# v4_3.net
KiCad netlist of a schematic drawn in EAGLE
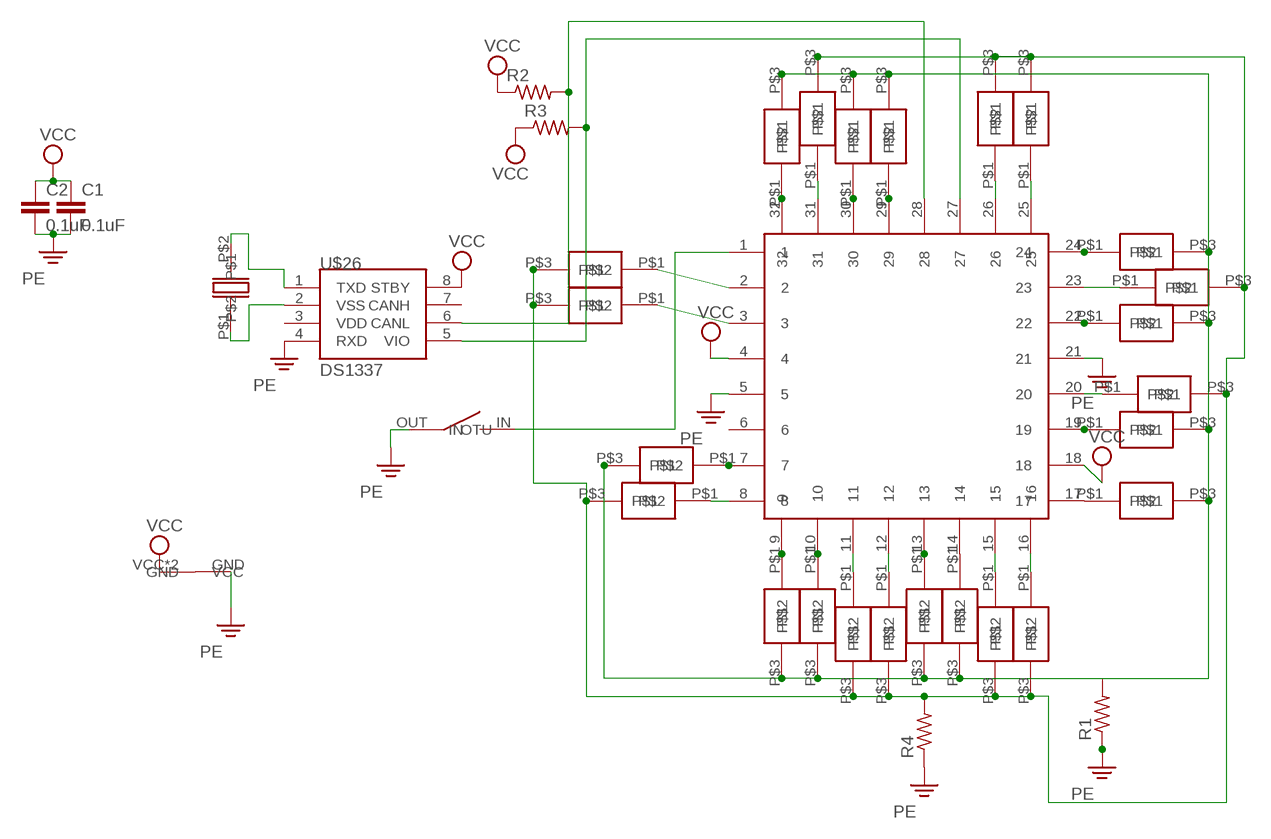
[diagram p0: schematic, sheet 1]

(export (version "E")
  (design (tool "Eeschema 10.0.6"))
  (components
    (comp (ref "C1")
      (value "0.1uF")
      (footprint "eagle-import:C0805K")
      (libsource (lib "eagle-import") (part "C-EUC0805K"))
    )
    (comp (ref "C2")
      (value "0.1uF")
      (footprint "eagle-import:C0805K")
      (libsource (lib "eagle-import") (part "C-EUC0805K"))
    )
    (comp (ref "R1")
      (value "R-US_R0805")
      (footprint "eagle-import:R0805")
      (libsource (lib "eagle-import") (part "R-US_R0805"))
    )
    (comp (ref "R2")
      (value "R-US_R0805")
      (footprint "eagle-import:R0805")
      (libsource (lib "eagle-import") (part "R-US_R0805"))
    )
    (comp (ref "R3")
      (value "R-US_R0805")
      (footprint "eagle-import:R0805")
      (libsource (lib "eagle-import") (part "R-US_R0805"))
    )
    (comp (ref "R4")
      (value "R-US_R0805")
      (footprint "eagle-import:R0805")
      (libsource (lib "eagle-import") (part "R-US_R0805"))
    )
    (comp (ref "U$1")
      (value "SMDLED")
      (footprint "eagle-import:SMDLED")
      (libsource (lib "eagle-import") (part "SMDLED"))
    )
    (comp (ref "U$2")
      (value "SMDLED")
      (footprint "eagle-import:SMDLED")
      (libsource (lib "eagle-import") (part "SMDLED"))
    )
    (comp (ref "U$3")
      (value "SMDLED")
      (footprint "eagle-import:SMDLED")
      (libsource (lib "eagle-import") (part "SMDLED"))
    )
    (comp (ref "U$4")
      (value "SMDLED")
      (footprint "eagle-import:SMDLED")
      (libsource (lib "eagle-import") (part "SMDLED"))
    )
    (comp (ref "U$5")
      (value "SMDLED")
      (footprint "eagle-import:SMDLED")
      (libsource (lib "eagle-import") (part "SMDLED"))
    )
    (comp (ref "U$6")
      (value "SMDLED")
      (footprint "eagle-import:SMDLED")
      (libsource (lib "eagle-import") (part "SMDLED"))
    )
    (comp (ref "U$7")
      (value "SMDLED")
      (footprint "eagle-import:SMDLED")
      (libsource (lib "eagle-import") (part "SMDLED"))
    )
    (comp (ref "U$8")
      (value "SMDLED")
      (footprint "eagle-import:SMDLED")
      (libsource (lib "eagle-import") (part "SMDLED"))
    )
    (comp (ref "U$9")
      (value "SMDLED")
      (footprint "eagle-import:SMDLED")
      (libsource (lib "eagle-import") (part "SMDLED"))
    )
    (comp (ref "U$10")
      (value "SMDLED")
      (footprint "eagle-import:SMDLED")
      (libsource (lib "eagle-import") (part "SMDLED"))
    )
    (comp (ref "U$11")
      (value "SMDLED")
      (footprint "eagle-import:SMDLED")
      (libsource (lib "eagle-import") (part "SMDLED"))
    )
    (comp (ref "U$12")
      (value "SMDLED")
      (footprint "eagle-import:SMDLED")
      (libsource (lib "eagle-import") (part "SMDLED"))
    )
    (comp (ref "U$13")
      (value "SMDLED")
      (footprint "eagle-import:SMDLED")
      (libsource (lib "eagle-import") (part "SMDLED"))
    )
    (comp (ref "U$14")
      (value "SMDLED")
      (footprint "eagle-import:SMDLED")
      (libsource (lib "eagle-import") (part "SMDLED"))
    )
    (comp (ref "U$15")
      (value "SMDLED")
      (footprint "eagle-import:SMDLED")
      (libsource (lib "eagle-import") (part "SMDLED"))
    )
    (comp (ref "U$16")
      (value "SMDLED")
      (footprint "eagle-import:SMDLED")
      (libsource (lib "eagle-import") (part "SMDLED"))
    )
    (comp (ref "U$17")
      (value "SMDLED")
      (footprint "eagle-import:SMDLED")
      (libsource (lib "eagle-import") (part "SMDLED"))
    )
    (comp (ref "U$18")
      (value "SMDLED")
      (footprint "eagle-import:SMDLED")
      (libsource (lib "eagle-import") (part "SMDLED"))
    )
    (comp (ref "U$19")
      (value "SMDLED")
      (footprint "eagle-import:SMDLED")
      (libsource (lib "eagle-import") (part "SMDLED"))
    )
    (comp (ref "U$20")
      (value "SMDLED")
      (footprint "eagle-import:SMDLED")
      (libsource (lib "eagle-import") (part "SMDLED"))
    )
    (comp (ref "U$21")
      (value "SMDLED")
      (footprint "eagle-import:SMDLED")
      (libsource (lib "eagle-import") (part "SMDLED"))
    )
    (comp (ref "U$22")
      (value "SMDLED")
      (footprint "eagle-import:SMDLED")
      (libsource (lib "eagle-import") (part "SMDLED"))
    )
    (comp (ref "U$23")
      (value "SMDLED")
      (footprint "eagle-import:SMDLED")
      (libsource (lib "eagle-import") (part "SMDLED"))
    )
    (comp (ref "U$24")
      (value "SMDLED")
      (footprint "eagle-import:SMDLED")
      (libsource (lib "eagle-import") (part "SMDLED"))
    )
    (comp (ref "U$25")
      (value "ATTINY88")
      (footprint "eagle-import:32-TQFT")
      (libsource (lib "eagle-import") (part "ATTINY88"))
    )
    (comp (ref "U$26")
      (value "DS1337")
      (footprint "eagle-import:8-SOIC")
      (libsource (lib "eagle-import") (part "DS1337"))
    )
    (comp (ref "U$27")
      (value "BAT2009")
      (footprint "eagle-import:BAT2009")
      (libsource (lib "eagle-import") (part "BAT2009"))
    )
    (comp (ref "U$28")
      (value "INT2")
      (footprint "eagle-import:INT2")
      (libsource (lib "eagle-import") (part "INT2"))
    )
    (comp (ref "U$29")
      (value "SMDCRYSTAL")
      (footprint "eagle-import:SMDCRYSTAL")
      (libsource (lib "eagle-import") (part "SMDCRYSTAL"))
    )
  )
  (nets
    (net (code "1") (name "Net-(U$1-P$2)") (class "Default")
      (node (ref "R4") (pin "2") (pinfunction "2_2") (pintype "passive"))
      (node (ref "U$1") (pin "P$3") (pinfunction "P$2_P$3") (pintype "bidirectional"))
      (node (ref "U$10") (pin "P$3") (pinfunction "P$2_P$3") (pintype "bidirectional"))
      (node (ref "U$14") (pin "P$3") (pinfunction "P$2_P$3") (pintype "bidirectional"))
      (node (ref "U$16") (pin "P$3") (pinfunction "P$2_P$3") (pintype "bidirectional"))
      (node (ref "U$17") (pin "P$3") (pinfunction "P$2_P$3") (pintype "bidirectional"))
      (node (ref "U$20") (pin "P$3") (pinfunction "P$2_P$3") (pintype "bidirectional"))
      (node (ref "U$22") (pin "P$3") (pinfunction "P$2_P$3") (pintype "bidirectional"))
      (node (ref "U$24") (pin "P$3") (pinfunction "P$2_P$3") (pintype "bidirectional"))
      (node (ref "U$4") (pin "P$3") (pinfunction "P$2_P$3") (pintype "bidirectional"))
      (node (ref "U$5") (pin "P$3") (pinfunction "P$2_P$3") (pintype "bidirectional"))
      (node (ref "U$8") (pin "P$3") (pinfunction "P$2_P$3") (pintype "bidirectional"))
      (node (ref "U$9") (pin "P$3") (pinfunction "P$2_P$3") (pintype "bidirectional"))
    )
    (net (code "2") (name "Net-(U$1-PadP$1)") (class "Default")
      (node (ref "U$1") (pin "P$1") (pinfunction "P$1_P$1") (pintype "bidirectional"))
      (node (ref "U$25") (pin "12") (pinfunction "12_12") (pintype "bidirectional"))
    )
    (net (code "3") (name "Net-(U$2-PadP$1)") (class "Default")
      (node (ref "U$2") (pin "P$1") (pinfunction "P$1_P$1") (pintype "bidirectional"))
      (node (ref "U$25") (pin "13") (pinfunction "13_13") (pintype "bidirectional"))
    )
    (net (code "4") (name "Net-(U$10-PadP$1)") (class "Default")
      (node (ref "U$10") (pin "P$1") (pinfunction "P$1_P$1") (pintype "bidirectional"))
      (node (ref "U$25") (pin "20") (pinfunction "20_20") (pintype "bidirectional"))
    )
    (net (code "5") (name "Net-(U$11-P$2)") (class "Default")
      (node (ref "R1") (pin "2") (pinfunction "2_2") (pintype "passive"))
      (node (ref "U$11") (pin "P$3") (pinfunction "P$2_P$3") (pintype "bidirectional"))
      (node (ref "U$12") (pin "P$3") (pinfunction "P$2_P$3") (pintype "bidirectional"))
      (node (ref "U$13") (pin "P$3") (pinfunction "P$2_P$3") (pintype "bidirectional"))
      (node (ref "U$15") (pin "P$3") (pinfunction "P$2_P$3") (pintype "bidirectional"))
      (node (ref "U$18") (pin "P$3") (pinfunction "P$2_P$3") (pintype "bidirectional"))
      (node (ref "U$19") (pin "P$3") (pinfunction "P$2_P$3") (pintype "bidirectional"))
      (node (ref "U$2") (pin "P$3") (pinfunction "P$2_P$3") (pintype "bidirectional"))
      (node (ref "U$21") (pin "P$3") (pinfunction "P$2_P$3") (pintype "bidirectional"))
      (node (ref "U$23") (pin "P$3") (pinfunction "P$2_P$3") (pintype "bidirectional"))
      (node (ref "U$3") (pin "P$3") (pinfunction "P$2_P$3") (pintype "bidirectional"))
      (node (ref "U$6") (pin "P$3") (pinfunction "P$2_P$3") (pintype "bidirectional"))
      (node (ref "U$7") (pin "P$3") (pinfunction "P$2_P$3") (pintype "bidirectional"))
    )
    (net (code "6") (name "Net-(U$11-PadP$1)") (class "Default")
      (node (ref "U$11") (pin "P$1") (pinfunction "P$1_P$1") (pintype "bidirectional"))
      (node (ref "U$25") (pin "17") (pinfunction "17_17") (pintype "bidirectional"))
    )
    (net (code "7") (name "Net-(U$12-PadP$1)") (class "Default")
      (node (ref "U$12") (pin "P$1") (pinfunction "P$1_P$1") (pintype "bidirectional"))
      (node (ref "U$25") (pin "19") (pinfunction "19_19") (pintype "bidirectional"))
    )
    (net (code "8") (name "Net-(U$13-PadP$1)") (class "Default")
      (node (ref "U$13") (pin "P$1") (pinfunction "P$1_P$1") (pintype "bidirectional"))
      (node (ref "U$25") (pin "30") (pinfunction "30_30") (pintype "bidirectional"))
    )
    (net (code "9") (name "Net-(U$14-PadP$1)") (class "Default")
      (node (ref "U$14") (pin "P$1") (pinfunction "P$1_P$1") (pintype "bidirectional"))
      (node (ref "U$25") (pin "31") (pinfunction "31_31") (pintype "bidirectional"))
    )
    (net (code "10") (name "Net-(U$15-PadP$1)") (class "Default")
      (node (ref "U$15") (pin "P$1") (pinfunction "P$1_P$1") (pintype "bidirectional"))
      (node (ref "U$25") (pin "32") (pinfunction "32_32") (pintype "bidirectional"))
    )
    (net (code "11") (name "Net-(U$16-PadP$1)") (class "Default")
      (node (ref "U$16") (pin "P$1") (pinfunction "P$1_P$1") (pintype "bidirectional"))
      (node (ref "U$25") (pin "2") (pinfunction "2_2") (pintype "bidirectional"))
    )
    (net (code "12") (name "Net-(U$17-PadP$1)") (class "Default")
      (node (ref "U$17") (pin "P$1") (pinfunction "P$1_P$1") (pintype "bidirectional"))
      (node (ref "U$25") (pin "3") (pinfunction "3_3") (pintype "bidirectional"))
    )
    (net (code "13") (name "Net-(U$18-PadP$1)") (class "Default")
      (node (ref "U$18") (pin "P$1") (pinfunction "P$1_P$1") (pintype "bidirectional"))
      (node (ref "U$25") (pin "9") (pinfunction "9_9") (pintype "bidirectional"))
    )
    (net (code "14") (name "Net-(U$19-PadP$1)") (class "Default")
      (node (ref "U$19") (pin "P$1") (pinfunction "P$1_P$1") (pintype "bidirectional"))
      (node (ref "U$25") (pin "10") (pinfunction "10_10") (pintype "bidirectional"))
    )
    (net (code "15") (name "Net-(U$20-PadP$1)") (class "Default")
      (node (ref "U$20") (pin "P$1") (pinfunction "P$1_P$1") (pintype "bidirectional"))
      (node (ref "U$25") (pin "11") (pinfunction "11_11") (pintype "bidirectional"))
    )
    (net (code "16") (name "Net-(U$21-PadP$1)") (class "Default")
      (node (ref "U$21") (pin "P$1") (pinfunction "P$1_P$1") (pintype "bidirectional"))
      (node (ref "U$25") (pin "22") (pinfunction "22_22") (pintype "bidirectional"))
    )
    (net (code "17") (name "Net-(U$22-PadP$1)") (class "Default")
      (node (ref "U$22") (pin "P$1") (pinfunction "P$1_P$1") (pintype "bidirectional"))
      (node (ref "U$25") (pin "23") (pinfunction "23_23") (pintype "bidirectional"))
    )
    (net (code "18") (name "Net-(U$23-PadP$1)") (class "Default")
      (node (ref "U$23") (pin "P$1") (pinfunction "P$1_P$1") (pintype "bidirectional"))
      (node (ref "U$25") (pin "29") (pinfunction "29_29") (pintype "bidirectional"))
    )
    (net (code "19") (name "Net-(U$24-PadP$1)") (class "Default")
      (node (ref "U$24") (pin "P$1") (pinfunction "P$1_P$1") (pintype "bidirectional"))
      (node (ref "U$25") (pin "26") (pinfunction "26_26") (pintype "bidirectional"))
    )
    (net (code "20") (name "Net-(U$25-Pad1)") (class "Default")
      (node (ref "U$25") (pin "1") (pinfunction "1_1") (pintype "bidirectional"))
      (node (ref "U$28") (pin "IN") (pinfunction "IN_IN") (pintype "bidirectional"))
    )
    (net (code "21") (name "Net-(U$25-Pad7)") (class "Default")
      (node (ref "U$25") (pin "7") (pinfunction "7_7") (pintype "bidirectional"))
      (node (ref "U$7") (pin "P$1") (pinfunction "P$1_P$1") (pintype "bidirectional"))
    )
    (net (code "22") (name "Net-(U$25-Pad8)") (class "Default")
      (node (ref "U$25") (pin "8") (pinfunction "8_8") (pintype "bidirectional"))
      (node (ref "U$8") (pin "P$1") (pinfunction "P$1_P$1") (pintype "bidirectional"))
    )
    (net (code "23") (name "Net-(U$25-Pad14)") (class "Default")
      (node (ref "U$25") (pin "14") (pinfunction "14_14") (pintype "bidirectional"))
      (node (ref "U$3") (pin "P$1") (pinfunction "P$1_P$1") (pintype "bidirectional"))
    )
    (net (code "24") (name "Net-(U$25-Pad15)") (class "Default")
      (node (ref "U$25") (pin "15") (pinfunction "15_15") (pintype "bidirectional"))
      (node (ref "U$4") (pin "P$1") (pinfunction "P$1_P$1") (pintype "bidirectional"))
    )
    (net (code "25") (name "Net-(U$25-Pad16)") (class "Default")
      (node (ref "U$25") (pin "16") (pinfunction "16_16") (pintype "bidirectional"))
      (node (ref "U$5") (pin "P$1") (pinfunction "P$1_P$1") (pintype "bidirectional"))
    )
    (net (code "26") (name "Net-(U$25-Pad24)") (class "Default")
      (node (ref "U$25") (pin "24") (pinfunction "24_24") (pintype "bidirectional"))
      (node (ref "U$6") (pin "P$1") (pinfunction "P$1_P$1") (pintype "bidirectional"))
    )
    (net (code "27") (name "Net-(U$25-Pad25)") (class "Default")
      (node (ref "U$25") (pin "25") (pinfunction "25_25") (pintype "bidirectional"))
      (node (ref "U$9") (pin "P$1") (pinfunction "P$1_P$1") (pintype "bidirectional"))
    )
    (net (code "28") (name "Net-(U$26-CANL)") (class "Default")
      (node (ref "R2") (pin "2") (pinfunction "2_2") (pintype "passive"))
      (node (ref "U$25") (pin "28") (pinfunction "28_28") (pintype "bidirectional"))
      (node (ref "U$26") (pin "6") (pinfunction "CANL_6") (pintype "bidirectional"))
    )
    (net (code "29") (name "Net-(U$26-TXD)") (class "Default")
      (node (ref "U$26") (pin "1") (pinfunction "TXD_1") (pintype "bidirectional"))
      (node (ref "U$29") (pin "P$2") (pinfunction "P$2_P$2") (pintype "bidirectional"))
    )
    (net (code "30") (name "Net-(U$26-VIO)") (class "Default")
      (node (ref "R3") (pin "2") (pinfunction "2_2") (pintype "passive"))
      (node (ref "U$25") (pin "27") (pinfunction "27_27") (pintype "bidirectional"))
      (node (ref "U$26") (pin "5") (pinfunction "VIO_5") (pintype "bidirectional"))
    )
    (net (code "31") (name "Net-(U$26-VSS)") (class "Default")
      (node (ref "U$26") (pin "2") (pinfunction "VSS_2") (pintype "bidirectional"))
      (node (ref "U$29") (pin "P$1") (pinfunction "P$1_P$1") (pintype "bidirectional"))
    )
    (net (code "32") (name "PE") (class "Default")
      (node (ref "C1") (pin "2") (pinfunction "2_2") (pintype "passive"))
      (node (ref "C2") (pin "2") (pinfunction "2_2") (pintype "passive"))
      (node (ref "R1") (pin "1") (pinfunction "1_1") (pintype "passive"))
      (node (ref "R4") (pin "1") (pinfunction "1_1") (pintype "passive"))
      (node (ref "U$25") (pin "21") (pinfunction "21_21") (pintype "bidirectional"))
      (node (ref "U$25") (pin "5") (pinfunction "5_5") (pintype "bidirectional"))
      (node (ref "U$26") (pin "4") (pinfunction "RXD_4") (pintype "bidirectional"))
      (node (ref "U$27") (pin "GND") (pinfunction "GND_GND") (pintype "bidirectional"))
      (node (ref "U$28") (pin "OUT") (pinfunction "OTU_OUT") (pintype "bidirectional"))
    )
    (net (code "33") (name "VCC") (class "Default")
      (node (ref "C1") (pin "1") (pinfunction "1_1") (pintype "passive"))
      (node (ref "C2") (pin "1") (pinfunction "1_1") (pintype "passive"))
      (node (ref "R2") (pin "1") (pinfunction "1_1") (pintype "passive"))
      (node (ref "R3") (pin "1") (pinfunction "1_1") (pintype "passive"))
      (node (ref "U$25") (pin "18") (pinfunction "18_18") (pintype "bidirectional"))
      (node (ref "U$25") (pin "4") (pinfunction "4_4") (pintype "bidirectional"))
      (node (ref "U$26") (pin "8") (pinfunction "STBY_8") (pintype "bidirectional"))
      (node (ref "U$27") (pin "VCC") (pinfunction "VCC_VCC") (pintype "bidirectional"))
      (node (ref "U$27") (pin "VCC2") (pinfunction "VCC_VCC2") (pintype "bidirectional"))
    )
    (net (code "34") (name "unconnected-(U$25-Pad6)") (class "Default")
      (node (ref "U$25") (pin "6") (pinfunction "6_6") (pintype "bidirectional"))
    )
    (net (code "35") (name "unconnected-(U$26-CANH-Pad7)") (class "Default")
      (node (ref "U$26") (pin "7") (pinfunction "CANH_7") (pintype "bidirectional"))
    )
    (net (code "36") (name "unconnected-(U$26-VDD-Pad3)") (class "Default")
      (node (ref "U$26") (pin "3") (pinfunction "VDD_3") (pintype "bidirectional"))
    )
  )
)
